# expansion_connectors.net
KiCad netlist of a schematic drawn in Altium Designer
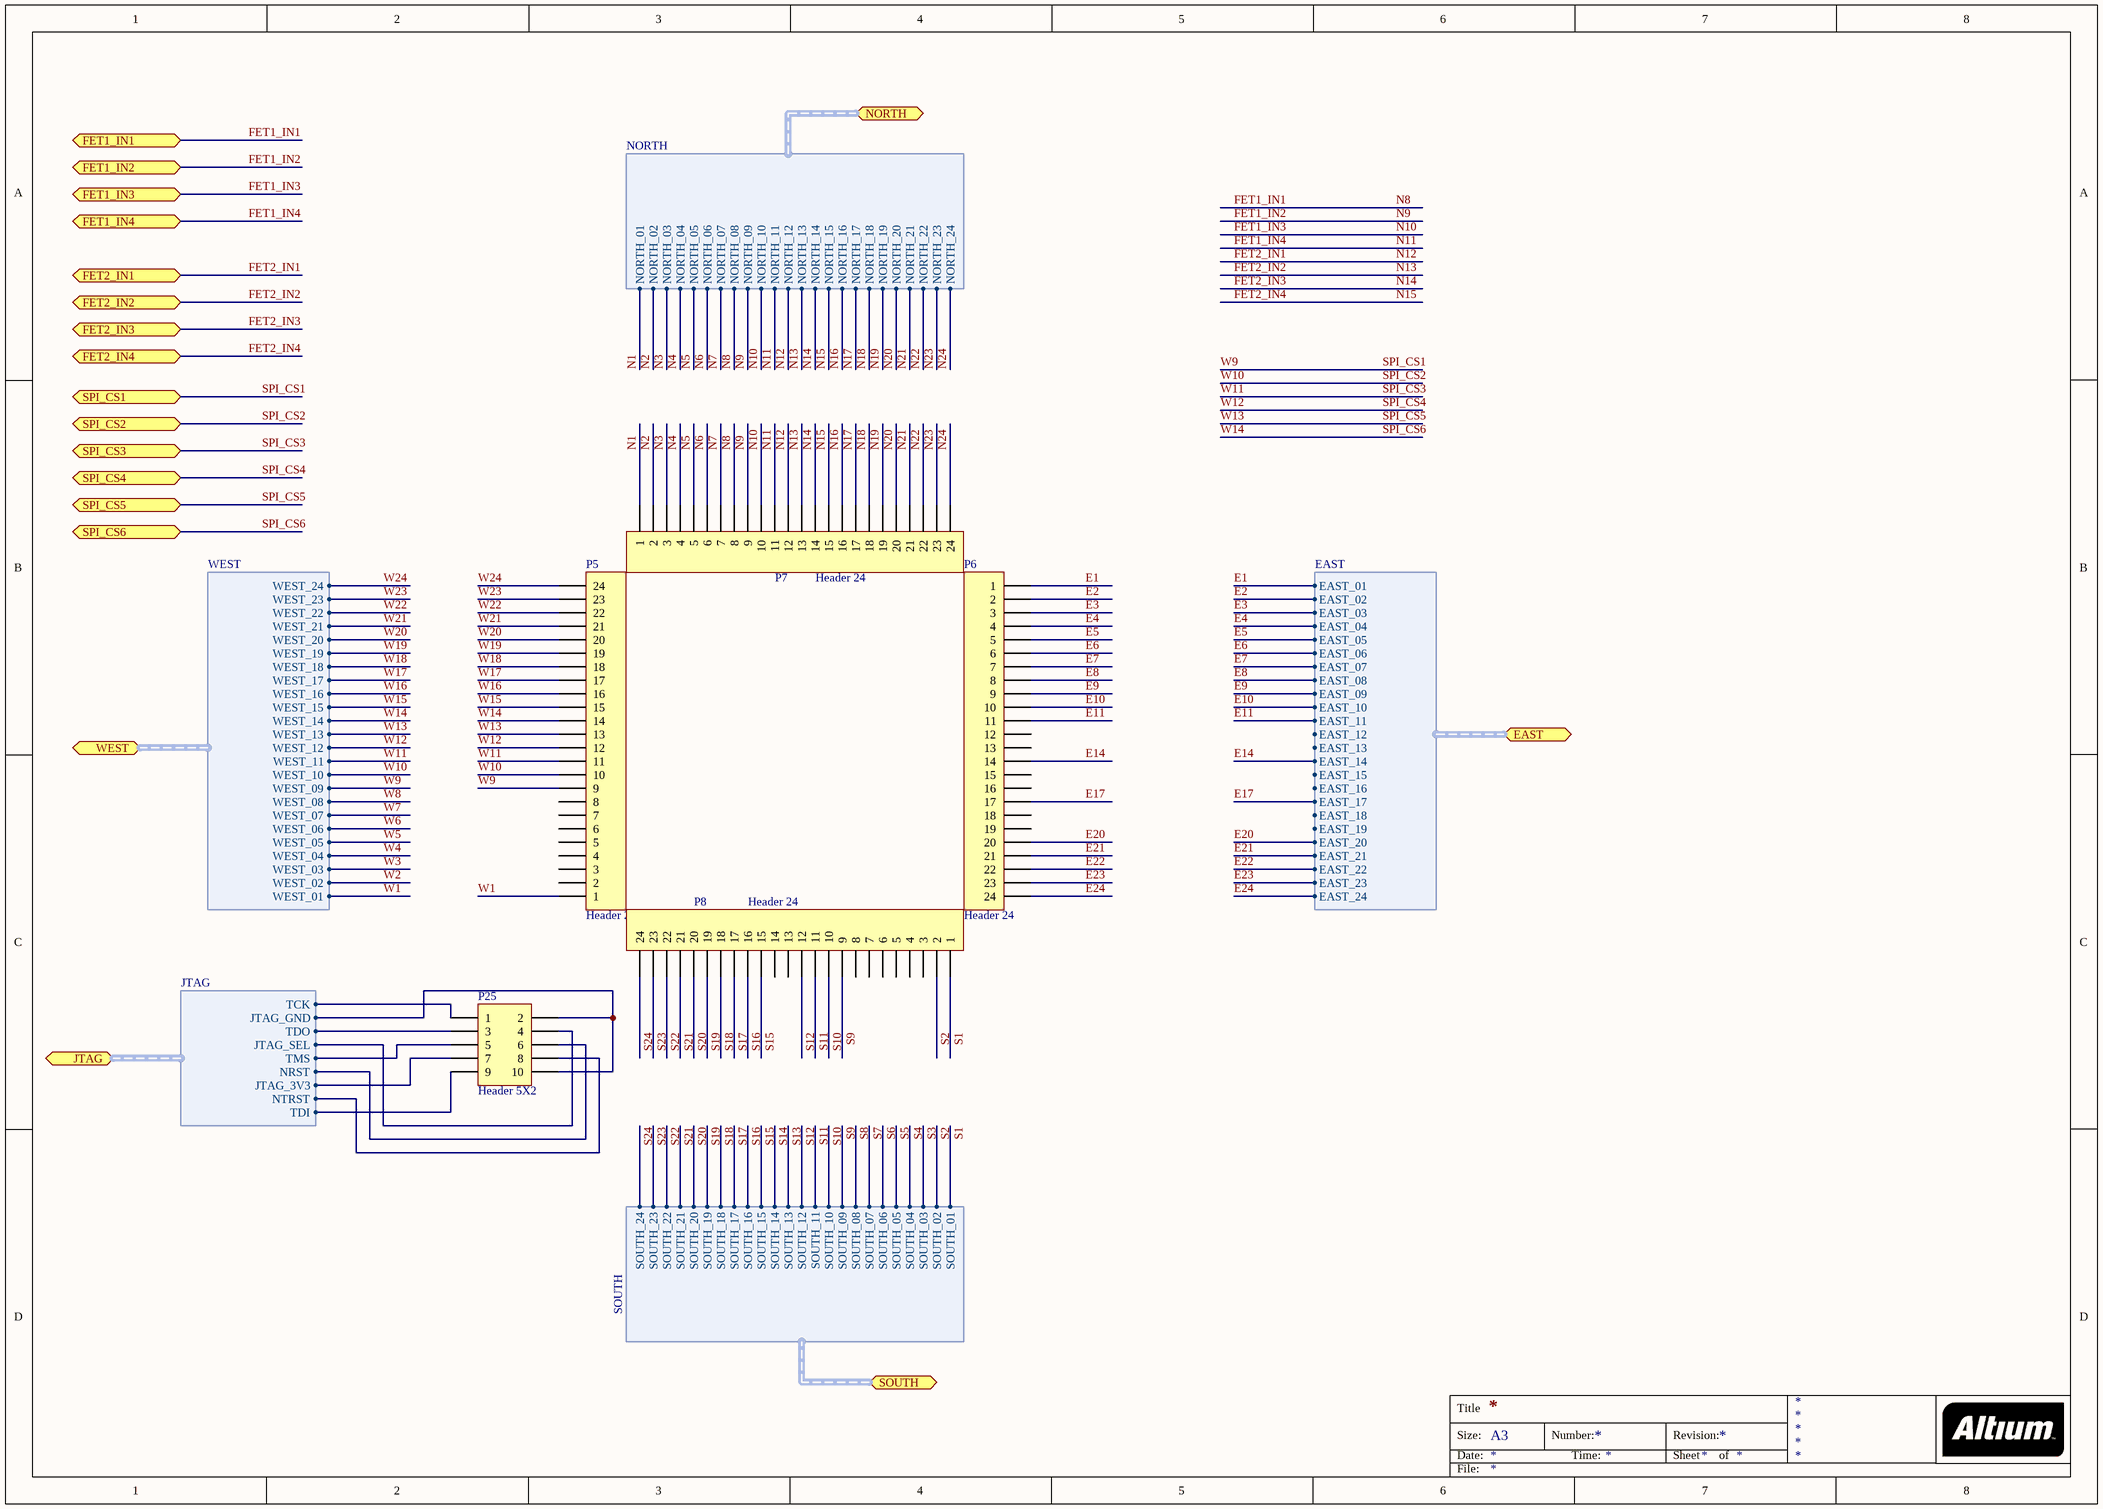
[diagram p0: expansion_connectors.SchDoc]

(export (version "E")
  (design (tool "Eeschema 10.0.6"))
  (components
    (comp (ref "P5")
      (value "Header 24")
      (footprint "HDR1X24")
      (description "Header, 24-Pin")
      (fields (field (name "PUBLISHER") "Altium Limited"))
      (libsource (lib "") (part "Header 24_3"))
    )
    (comp (ref "P6")
      (value "Header 24")
      (footprint "HDR1X24")
      (description "Header, 24-Pin")
      (fields (field (name "PUBLISHER") "Altium Limited"))
      (libsource (lib "") (part "Header 24_1"))
    )
    (comp (ref "P7")
      (value "Header 24")
      (footprint "HDR1X24")
      (description "Header, 24-Pin")
      (fields (field (name "PUBLISHER") "Altium Limited"))
      (libsource (lib "") (part "Header 24_2"))
    )
    (comp (ref "P8")
      (value "Header 24")
      (footprint "HDR1X24")
      (description "Header, 24-Pin")
      (fields (field (name "PUBLISHER") "Altium Limited"))
      (libsource (lib "Miscellaneous Connectors") (part "Header 24"))
    )
    (comp (ref "P25")
      (value "Header 5X2")
      (footprint "HDR2X5")
      (description "Header, 5-Pin, Dual row")
      (fields (field (name "PUBLISHER") "Altium Limited"))
      (libsource (lib "Miscellaneous Connectors") (part "Header 5X2"))
    )
  )
  (nets
    (net (code "6") (name "/E1") (class "Default")
      (node (ref "P6") (pin "1") (pinfunction "1_1") (pintype "passive"))
    )
    (net (code "7") (name "/E2") (class "Default")
      (node (ref "P6") (pin "2") (pinfunction "2_2") (pintype "passive"))
    )
    (net (code "8") (name "/E3") (class "Default")
      (node (ref "P6") (pin "3") (pinfunction "3_3") (pintype "passive"))
    )
    (net (code "9") (name "/E4") (class "Default")
      (node (ref "P6") (pin "4") (pinfunction "4_4") (pintype "passive"))
    )
    (net (code "10") (name "/E5") (class "Default")
      (node (ref "P6") (pin "5") (pinfunction "5_5") (pintype "passive"))
    )
    (net (code "11") (name "/E6") (class "Default")
      (node (ref "P6") (pin "6") (pinfunction "6_6") (pintype "passive"))
    )
    (net (code "12") (name "/E7") (class "Default")
      (node (ref "P6") (pin "7") (pinfunction "7_7") (pintype "passive"))
    )
    (net (code "13") (name "/E8") (class "Default")
      (node (ref "P6") (pin "8") (pinfunction "8_8") (pintype "passive"))
    )
    (net (code "14") (name "/E9") (class "Default")
      (node (ref "P6") (pin "9") (pinfunction "9_9") (pintype "passive"))
    )
    (net (code "15") (name "/E10") (class "Default")
      (node (ref "P6") (pin "10") (pinfunction "10_10") (pintype "passive"))
    )
    (net (code "16") (name "/E11") (class "Default")
      (node (ref "P6") (pin "11") (pinfunction "11_11") (pintype "passive"))
    )
    (net (code "17") (name "/E14") (class "Default")
      (node (ref "P6") (pin "14") (pinfunction "14_14") (pintype "passive"))
    )
    (net (code "18") (name "/E17") (class "Default")
      (node (ref "P6") (pin "17") (pinfunction "17_17") (pintype "passive"))
    )
    (net (code "19") (name "/E20") (class "Default")
      (node (ref "P6") (pin "20") (pinfunction "20_20") (pintype "passive"))
    )
    (net (code "20") (name "/E21") (class "Default")
      (node (ref "P6") (pin "21") (pinfunction "21_21") (pintype "passive"))
    )
    (net (code "21") (name "/E22") (class "Default")
      (node (ref "P6") (pin "22") (pinfunction "22_22") (pintype "passive"))
    )
    (net (code "22") (name "/E23") (class "Default")
      (node (ref "P6") (pin "23") (pinfunction "23_23") (pintype "passive"))
    )
    (net (code "23") (name "/E24") (class "Default")
      (node (ref "P6") (pin "24") (pinfunction "24_24") (pintype "passive"))
    )
    (net (code "24") (name "/FET1_IN1") (class "Default")
      (node (ref "P7") (pin "8") (pinfunction "8_8") (pintype "passive"))
    )
    (net (code "25") (name "/FET1_IN2") (class "Default")
      (node (ref "P7") (pin "9") (pinfunction "9_9") (pintype "passive"))
    )
    (net (code "26") (name "/FET1_IN3") (class "Default")
      (node (ref "P7") (pin "10") (pinfunction "10_10") (pintype "passive"))
    )
    (net (code "27") (name "/FET1_IN4") (class "Default")
      (node (ref "P7") (pin "11") (pinfunction "11_11") (pintype "passive"))
    )
    (net (code "28") (name "/FET2_IN1") (class "Default")
      (node (ref "P7") (pin "12") (pinfunction "12_12") (pintype "passive"))
    )
    (net (code "29") (name "/FET2_IN2") (class "Default")
      (node (ref "P7") (pin "13") (pinfunction "13_13") (pintype "passive"))
    )
    (net (code "30") (name "/FET2_IN3") (class "Default")
      (node (ref "P7") (pin "14") (pinfunction "14_14") (pintype "passive"))
    )
    (net (code "31") (name "/FET2_IN4") (class "Default")
      (node (ref "P7") (pin "15") (pinfunction "15_15") (pintype "passive"))
    )
    (net (code "32") (name "/JTAG_3V3") (class "Default")
      (node (ref "P25") (pin "7") (pinfunction "7_7") (pintype "passive"))
    )
    (net (code "33") (name "/JTAG_GND") (class "Default")
      (node (ref "P25") (pin "10") (pinfunction "10_10") (pintype "passive"))
      (node (ref "P25") (pin "2") (pinfunction "2_2") (pintype "passive"))
    )
    (net (code "34") (name "/JTAG_SEL") (class "Default")
      (node (ref "P25") (pin "4") (pinfunction "4_4") (pintype "passive"))
    )
    (net (code "35") (name "/N1") (class "Default")
      (node (ref "P7") (pin "1") (pinfunction "1_1") (pintype "passive"))
    )
    (net (code "36") (name "/N2") (class "Default")
      (node (ref "P7") (pin "2") (pinfunction "2_2") (pintype "passive"))
    )
    (net (code "37") (name "/N3") (class "Default")
      (node (ref "P7") (pin "3") (pinfunction "3_3") (pintype "passive"))
    )
    (net (code "38") (name "/N4") (class "Default")
      (node (ref "P7") (pin "4") (pinfunction "4_4") (pintype "passive"))
    )
    (net (code "39") (name "/N5") (class "Default")
      (node (ref "P7") (pin "5") (pinfunction "5_5") (pintype "passive"))
    )
    (net (code "40") (name "/N6") (class "Default")
      (node (ref "P7") (pin "6") (pinfunction "6_6") (pintype "passive"))
    )
    (net (code "41") (name "/N7") (class "Default")
      (node (ref "P7") (pin "7") (pinfunction "7_7") (pintype "passive"))
    )
    (net (code "42") (name "/N16") (class "Default")
      (node (ref "P7") (pin "16") (pinfunction "16_16") (pintype "passive"))
    )
    (net (code "43") (name "/N17") (class "Default")
      (node (ref "P7") (pin "17") (pinfunction "17_17") (pintype "passive"))
    )
    (net (code "44") (name "/N18") (class "Default")
      (node (ref "P7") (pin "18") (pinfunction "18_18") (pintype "passive"))
    )
    (net (code "45") (name "/N19") (class "Default")
      (node (ref "P7") (pin "19") (pinfunction "19_19") (pintype "passive"))
    )
    (net (code "46") (name "/N20") (class "Default")
      (node (ref "P7") (pin "20") (pinfunction "20_20") (pintype "passive"))
    )
    (net (code "47") (name "/N21") (class "Default")
      (node (ref "P7") (pin "21") (pinfunction "21_21") (pintype "passive"))
    )
    (net (code "48") (name "/N22") (class "Default")
      (node (ref "P7") (pin "22") (pinfunction "22_22") (pintype "passive"))
    )
    (net (code "49") (name "/N23") (class "Default")
      (node (ref "P7") (pin "23") (pinfunction "23_23") (pintype "passive"))
    )
    (net (code "50") (name "/N24") (class "Default")
      (node (ref "P7") (pin "24") (pinfunction "24_24") (pintype "passive"))
    )
    (net (code "51") (name "/NRST") (class "Default")
      (node (ref "P25") (pin "6") (pinfunction "6_6") (pintype "passive"))
    )
    (net (code "52") (name "/NTRST") (class "Default")
      (node (ref "P25") (pin "8") (pinfunction "8_8") (pintype "passive"))
    )
    (net (code "53") (name "/S1") (class "Default")
      (node (ref "P8") (pin "1") (pinfunction "1_1") (pintype "passive"))
    )
    (net (code "54") (name "/S2") (class "Default")
      (node (ref "P8") (pin "2") (pinfunction "2_2") (pintype "passive"))
    )
    (net (code "61") (name "/S9") (class "Default")
      (node (ref "P8") (pin "9") (pinfunction "9_9") (pintype "passive"))
    )
    (net (code "62") (name "/S10") (class "Default")
      (node (ref "P8") (pin "10") (pinfunction "10_10") (pintype "passive"))
    )
    (net (code "63") (name "/S11") (class "Default")
      (node (ref "P8") (pin "11") (pinfunction "11_11") (pintype "passive"))
    )
    (net (code "64") (name "/S12") (class "Default")
      (node (ref "P8") (pin "12") (pinfunction "12_12") (pintype "passive"))
    )
    (net (code "67") (name "/S15") (class "Default")
      (node (ref "P8") (pin "15") (pinfunction "15_15") (pintype "passive"))
    )
    (net (code "68") (name "/S16") (class "Default")
      (node (ref "P8") (pin "16") (pinfunction "16_16") (pintype "passive"))
    )
    (net (code "69") (name "/S17") (class "Default")
      (node (ref "P8") (pin "17") (pinfunction "17_17") (pintype "passive"))
    )
    (net (code "70") (name "/S18") (class "Default")
      (node (ref "P8") (pin "18") (pinfunction "18_18") (pintype "passive"))
    )
    (net (code "71") (name "/S19") (class "Default")
      (node (ref "P8") (pin "19") (pinfunction "19_19") (pintype "passive"))
    )
    (net (code "72") (name "/S20") (class "Default")
      (node (ref "P8") (pin "20") (pinfunction "20_20") (pintype "passive"))
    )
    (net (code "73") (name "/S21") (class "Default")
      (node (ref "P8") (pin "21") (pinfunction "21_21") (pintype "passive"))
    )
    (net (code "74") (name "/S22") (class "Default")
      (node (ref "P8") (pin "22") (pinfunction "22_22") (pintype "passive"))
    )
    (net (code "75") (name "/S23") (class "Default")
      (node (ref "P8") (pin "23") (pinfunction "23_23") (pintype "passive"))
    )
    (net (code "76") (name "/S24") (class "Default")
      (node (ref "P8") (pin "24") (pinfunction "24_24") (pintype "passive"))
    )
    (net (code "77") (name "/SPI_CS1") (class "Default")
      (node (ref "P5") (pin "9") (pinfunction "9_9") (pintype "passive"))
    )
    (net (code "78") (name "/SPI_CS2") (class "Default")
      (node (ref "P5") (pin "10") (pinfunction "10_10") (pintype "passive"))
    )
    (net (code "79") (name "/SPI_CS3") (class "Default")
      (node (ref "P5") (pin "11") (pinfunction "11_11") (pintype "passive"))
    )
    (net (code "80") (name "/SPI_CS4") (class "Default")
      (node (ref "P5") (pin "12") (pinfunction "12_12") (pintype "passive"))
    )
    (net (code "81") (name "/SPI_CS5") (class "Default")
      (node (ref "P5") (pin "13") (pinfunction "13_13") (pintype "passive"))
    )
    (net (code "82") (name "/SPI_CS6") (class "Default")
      (node (ref "P5") (pin "14") (pinfunction "14_14") (pintype "passive"))
    )
    (net (code "83") (name "/TCK") (class "Default")
      (node (ref "P25") (pin "1") (pinfunction "1_1") (pintype "passive"))
    )
    (net (code "84") (name "/TDI") (class "Default")
      (node (ref "P25") (pin "9") (pinfunction "9_9") (pintype "passive"))
    )
    (net (code "85") (name "/TDO") (class "Default")
      (node (ref "P25") (pin "3") (pinfunction "3_3") (pintype "passive"))
    )
    (net (code "86") (name "/TMS") (class "Default")
      (node (ref "P25") (pin "5") (pinfunction "5_5") (pintype "passive"))
    )
    (net (code "87") (name "/W1") (class "Default")
      (node (ref "P5") (pin "1") (pinfunction "1_1") (pintype "passive"))
    )
    (net (code "95") (name "/W15") (class "Default")
      (node (ref "P5") (pin "15") (pinfunction "15_15") (pintype "passive"))
    )
    (net (code "96") (name "/W16") (class "Default")
      (node (ref "P5") (pin "16") (pinfunction "16_16") (pintype "passive"))
    )
    (net (code "97") (name "/W17") (class "Default")
      (node (ref "P5") (pin "17") (pinfunction "17_17") (pintype "passive"))
    )
    (net (code "98") (name "/W18") (class "Default")
      (node (ref "P5") (pin "18") (pinfunction "18_18") (pintype "passive"))
    )
    (net (code "99") (name "/W19") (class "Default")
      (node (ref "P5") (pin "19") (pinfunction "19_19") (pintype "passive"))
    )
    (net (code "100") (name "/W20") (class "Default")
      (node (ref "P5") (pin "20") (pinfunction "20_20") (pintype "passive"))
    )
    (net (code "101") (name "/W21") (class "Default")
      (node (ref "P5") (pin "21") (pinfunction "21_21") (pintype "passive"))
    )
    (net (code "102") (name "/W22") (class "Default")
      (node (ref "P5") (pin "22") (pinfunction "22_22") (pintype "passive"))
    )
    (net (code "103") (name "/W23") (class "Default")
      (node (ref "P5") (pin "23") (pinfunction "23_23") (pintype "passive"))
    )
    (net (code "104") (name "/W24") (class "Default")
      (node (ref "P5") (pin "24") (pinfunction "24_24") (pintype "passive"))
    )
    (net (code "110") (name "unconnected-(P5-Pad2)") (class "Default")
      (node (ref "P5") (pin "2") (pinfunction "2_2") (pintype "passive"))
    )
    (net (code "111") (name "unconnected-(P5-Pad3)") (class "Default")
      (node (ref "P5") (pin "3") (pinfunction "3_3") (pintype "passive"))
    )
    (net (code "112") (name "unconnected-(P5-Pad4)") (class "Default")
      (node (ref "P5") (pin "4") (pinfunction "4_4") (pintype "passive"))
    )
    (net (code "113") (name "unconnected-(P5-Pad5)") (class "Default")
      (node (ref "P5") (pin "5") (pinfunction "5_5") (pintype "passive"))
    )
    (net (code "114") (name "unconnected-(P5-Pad6)") (class "Default")
      (node (ref "P5") (pin "6") (pinfunction "6_6") (pintype "passive"))
    )
    (net (code "115") (name "unconnected-(P5-Pad7)") (class "Default")
      (node (ref "P5") (pin "7") (pinfunction "7_7") (pintype "passive"))
    )
    (net (code "116") (name "unconnected-(P5-Pad8)") (class "Default")
      (node (ref "P5") (pin "8") (pinfunction "8_8") (pintype "passive"))
    )
    (net (code "117") (name "unconnected-(P6-Pad12)") (class "Default")
      (node (ref "P6") (pin "12") (pinfunction "12_12") (pintype "passive"))
    )
    (net (code "118") (name "unconnected-(P6-Pad13)") (class "Default")
      (node (ref "P6") (pin "13") (pinfunction "13_13") (pintype "passive"))
    )
    (net (code "119") (name "unconnected-(P6-Pad15)") (class "Default")
      (node (ref "P6") (pin "15") (pinfunction "15_15") (pintype "passive"))
    )
    (net (code "120") (name "unconnected-(P6-Pad16)") (class "Default")
      (node (ref "P6") (pin "16") (pinfunction "16_16") (pintype "passive"))
    )
    (net (code "121") (name "unconnected-(P6-Pad18)") (class "Default")
      (node (ref "P6") (pin "18") (pinfunction "18_18") (pintype "passive"))
    )
    (net (code "122") (name "unconnected-(P6-Pad19)") (class "Default")
      (node (ref "P6") (pin "19") (pinfunction "19_19") (pintype "passive"))
    )
    (net (code "123") (name "unconnected-(P8-Pad3)") (class "Default")
      (node (ref "P8") (pin "3") (pinfunction "3_3") (pintype "passive"))
    )
    (net (code "124") (name "unconnected-(P8-Pad4)") (class "Default")
      (node (ref "P8") (pin "4") (pinfunction "4_4") (pintype "passive"))
    )
    (net (code "125") (name "unconnected-(P8-Pad5)") (class "Default")
      (node (ref "P8") (pin "5") (pinfunction "5_5") (pintype "passive"))
    )
    (net (code "126") (name "unconnected-(P8-Pad6)") (class "Default")
      (node (ref "P8") (pin "6") (pinfunction "6_6") (pintype "passive"))
    )
    (net (code "127") (name "unconnected-(P8-Pad7)") (class "Default")
      (node (ref "P8") (pin "7") (pinfunction "7_7") (pintype "passive"))
    )
    (net (code "128") (name "unconnected-(P8-Pad8)") (class "Default")
      (node (ref "P8") (pin "8") (pinfunction "8_8") (pintype "passive"))
    )
    (net (code "129") (name "unconnected-(P8-Pad13)") (class "Default")
      (node (ref "P8") (pin "13") (pinfunction "13_13") (pintype "passive"))
    )
    (net (code "130") (name "unconnected-(P8-Pad14)") (class "Default")
      (node (ref "P8") (pin "14") (pinfunction "14_14") (pintype "passive"))
    )
  )
)
